# WiFi_Bluetooth_ESP-WROOM-32.net
KiCad netlist of a schematic drawn in Altium Designer
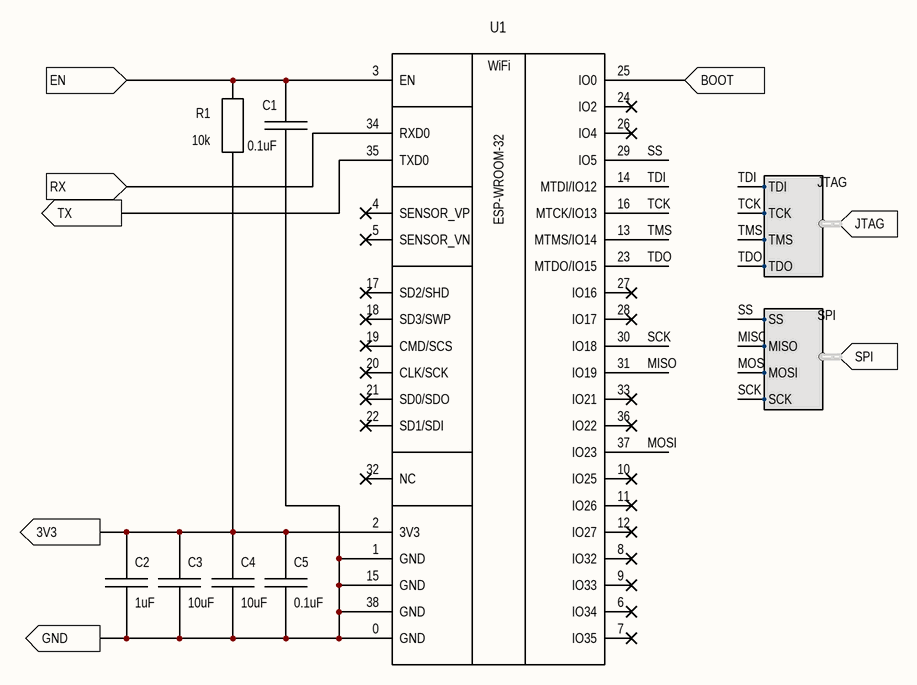
[diagram p0: WiFi Bluetooth ESP-WROOM-32.SchDoc]

(export (version "E")
  (design (tool "Eeschema 10.0.6"))
  (components
    (comp (ref "C1")
      (value "0.1uF")
      (footprint "CAPC1608L")
      (description "Capacitor Ceramic 0.1uF 25V 0603(1608)")
      (fields (field (name "TOLERANCE") "±10%") (field (name "VOLTAGE") "25"))
      (libsource (lib "Capacitors") (part "Capacitor Ceramic 0.1uF 25V 0603(1608)"))
    )
    (comp (ref "C2")
      (value "1uF")
      (footprint "CAPC1608L")
      (description "Capacitor Ceramic 1uF 25V 0603(1608)")
      (fields (field (name "TOLERANCE") "±10%") (field (name "VOLTAGE") "25V"))
      (libsource (lib "Capacitors") (part "Capacitor Ceramic 1uF 25V 0603(1608)"))
    )
    (comp (ref "C3")
      (value "10uF")
      (footprint "CAPC2012L")
      (description "Capacitor Ceramic 10uF 25V 0805(2012)")
      (fields (field (name "TOLERANCE") "±10%") (field (name "VOLTAGE") "25"))
      (libsource (lib "Capacitors") (part "Capacitor Ceramic 10uF 25V 0805(2012)"))
    )
    (comp (ref "C4")
      (value "10uF")
      (footprint "CAPC2012L")
      (description "Capacitor Ceramic 10uF 25V 0805(2012)")
      (fields (field (name "TOLERANCE") "±10%") (field (name "VOLTAGE") "25"))
      (libsource (lib "Capacitors") (part "Capacitor Ceramic 10uF 25V 0805(2012)"))
    )
    (comp (ref "C5")
      (value "0.1uF")
      (footprint "CAPC1608L")
      (description "Capacitor Ceramic 0.1uF 25V 0603(1608)")
      (fields (field (name "TOLERANCE") "±10%") (field (name "VOLTAGE") "25"))
      (libsource (lib "Capacitors") (part "Capacitor Ceramic 0.1uF 25V 0603(1608)"))
    )
    (comp (ref "R1")
      (value "10k")
      (footprint "RESC1608L")
      (description "Resistor Ceramic 10k 0.1W 0603(1608)")
      (fields (field (name "TOLERANCE") "±5%") (field (name "POWER") "0.1W"))
      (libsource (lib "Resistors") (part "Resistor Ceramic 10k 0.1W 0603(1608)"))
    )
    (comp (ref "U1")
      (value "ESP-WROOM-32")
      (description "WiFi/Bluetooth Module based on ESP32")
      (fields (field (name "MANUFACTURER") "Espressif"))
      (libsource (lib "Wireless") (part "ESP-WROOM-32"))
    )
  )
  (nets
    (net (code "3") (name "/3V3") (class "Default")
      (node (ref "C2") (pin "1") (pinfunction "1_1") (pintype "passive"))
      (node (ref "C3") (pin "1") (pinfunction "1_1") (pintype "passive"))
      (node (ref "C4") (pin "1") (pinfunction "1_1") (pintype "passive"))
      (node (ref "C5") (pin "1") (pinfunction "1_1") (pintype "passive"))
      (node (ref "R1") (pin "2") (pinfunction "2_2") (pintype "passive"))
      (node (ref "U1") (pin "2") (pinfunction "3V3_2") (pintype "passive"))
    )
    (net (code "4") (name "/BOOT") (class "Default")
      (node (ref "U1") (pin "25") (pinfunction "IO0_25") (pintype "passive"))
    )
    (net (code "5") (name "/EN") (class "Default")
      (node (ref "C1") (pin "1") (pinfunction "1_1") (pintype "passive"))
      (node (ref "R1") (pin "1") (pinfunction "1_1") (pintype "passive"))
      (node (ref "U1") (pin "3") (pinfunction "EN_3") (pintype "passive"))
    )
    (net (code "6") (name "/GND") (class "Default")
      (node (ref "C1") (pin "2") (pinfunction "2_2") (pintype "passive"))
      (node (ref "C2") (pin "2") (pinfunction "2_2") (pintype "passive"))
      (node (ref "C3") (pin "2") (pinfunction "2_2") (pintype "passive"))
      (node (ref "C4") (pin "2") (pinfunction "2_2") (pintype "passive"))
      (node (ref "C5") (pin "2") (pinfunction "2_2") (pintype "passive"))
      (node (ref "U1") (pin "0") (pinfunction "GND_0") (pintype "passive"))
      (node (ref "U1") (pin "1") (pinfunction "GND_1") (pintype "passive"))
      (node (ref "U1") (pin "15") (pinfunction "GND_15") (pintype "passive"))
      (node (ref "U1") (pin "38") (pinfunction "GND_38") (pintype "passive"))
    )
    (net (code "7") (name "/MISO") (class "Default")
      (node (ref "U1") (pin "31") (pinfunction "IO19_31") (pintype "passive"))
    )
    (net (code "8") (name "/MOSI") (class "Default")
      (node (ref "U1") (pin "37") (pinfunction "IO23_37") (pintype "passive"))
    )
    (net (code "9") (name "/RX") (class "Default")
      (node (ref "U1") (pin "34") (pinfunction "RXD0_34") (pintype "passive"))
    )
    (net (code "10") (name "/SCK") (class "Default")
      (node (ref "U1") (pin "30") (pinfunction "IO18_30") (pintype "passive"))
    )
    (net (code "11") (name "/SS") (class "Default")
      (node (ref "U1") (pin "29") (pinfunction "IO5_29") (pintype "passive"))
    )
    (net (code "12") (name "/TCK") (class "Default")
      (node (ref "U1") (pin "16") (pinfunction "MTCK/IO13_16") (pintype "passive"))
    )
    (net (code "13") (name "/TDI") (class "Default")
      (node (ref "U1") (pin "14") (pinfunction "MTDI/IO12_14") (pintype "passive"))
    )
    (net (code "14") (name "/TDO") (class "Default")
      (node (ref "U1") (pin "23") (pinfunction "MTDO/IO15_23") (pintype "passive"))
    )
    (net (code "15") (name "/TMS") (class "Default")
      (node (ref "U1") (pin "13") (pinfunction "MTMS/IO14_13") (pintype "passive"))
    )
    (net (code "16") (name "/TX") (class "Default")
      (node (ref "U1") (pin "35") (pinfunction "TXD0_35") (pintype "passive"))
    )
    (net (code "19") (name "unconnected-(U1-CLK{slash}SCK-Pad20)") (class "Default")
      (node (ref "U1") (pin "20") (pinfunction "CLK/SCK_20") (pintype "passive+no_connect"))
    )
    (net (code "20") (name "unconnected-(U1-CMD{slash}SCS-Pad19)") (class "Default")
      (node (ref "U1") (pin "19") (pinfunction "CMD/SCS_19") (pintype "passive+no_connect"))
    )
    (net (code "21") (name "unconnected-(U1-IO2-Pad24)") (class "Default")
      (node (ref "U1") (pin "24") (pinfunction "IO2_24") (pintype "passive+no_connect"))
    )
    (net (code "22") (name "unconnected-(U1-IO4-Pad26)") (class "Default")
      (node (ref "U1") (pin "26") (pinfunction "IO4_26") (pintype "passive+no_connect"))
    )
    (net (code "23") (name "unconnected-(U1-IO16-Pad27)") (class "Default")
      (node (ref "U1") (pin "27") (pinfunction "IO16_27") (pintype "passive+no_connect"))
    )
    (net (code "24") (name "unconnected-(U1-IO17-Pad28)") (class "Default")
      (node (ref "U1") (pin "28") (pinfunction "IO17_28") (pintype "passive+no_connect"))
    )
    (net (code "25") (name "unconnected-(U1-IO21-Pad33)") (class "Default")
      (node (ref "U1") (pin "33") (pinfunction "IO21_33") (pintype "passive+no_connect"))
    )
    (net (code "26") (name "unconnected-(U1-IO22-Pad36)") (class "Default")
      (node (ref "U1") (pin "36") (pinfunction "IO22_36") (pintype "passive+no_connect"))
    )
    (net (code "27") (name "unconnected-(U1-IO25-Pad10)") (class "Default")
      (node (ref "U1") (pin "10") (pinfunction "IO25_10") (pintype "passive+no_connect"))
    )
    (net (code "28") (name "unconnected-(U1-IO26-Pad11)") (class "Default")
      (node (ref "U1") (pin "11") (pinfunction "IO26_11") (pintype "passive+no_connect"))
    )
    (net (code "29") (name "unconnected-(U1-IO27-Pad12)") (class "Default")
      (node (ref "U1") (pin "12") (pinfunction "IO27_12") (pintype "passive+no_connect"))
    )
    (net (code "30") (name "unconnected-(U1-IO32-Pad8)") (class "Default")
      (node (ref "U1") (pin "8") (pinfunction "IO32_8") (pintype "passive+no_connect"))
    )
    (net (code "31") (name "unconnected-(U1-IO33-Pad9)") (class "Default")
      (node (ref "U1") (pin "9") (pinfunction "IO33_9") (pintype "passive+no_connect"))
    )
    (net (code "32") (name "unconnected-(U1-IO34-Pad6)") (class "Default")
      (node (ref "U1") (pin "6") (pinfunction "IO34_6") (pintype "passive+no_connect"))
    )
    (net (code "33") (name "unconnected-(U1-IO35-Pad7)") (class "Default")
      (node (ref "U1") (pin "7") (pinfunction "IO35_7") (pintype "passive+no_connect"))
    )
    (net (code "34") (name "unconnected-(U1-NC-Pad32)") (class "Default")
      (node (ref "U1") (pin "32") (pinfunction "NC_32") (pintype "passive+no_connect"))
    )
    (net (code "35") (name "unconnected-(U1-SD0{slash}SDO-Pad21)") (class "Default")
      (node (ref "U1") (pin "21") (pinfunction "SD0/SDO_21") (pintype "passive+no_connect"))
    )
    (net (code "36") (name "unconnected-(U1-SD1{slash}SDI-Pad22)") (class "Default")
      (node (ref "U1") (pin "22") (pinfunction "SD1/SDI_22") (pintype "passive+no_connect"))
    )
    (net (code "37") (name "unconnected-(U1-SD2{slash}SHD-Pad17)") (class "Default")
      (node (ref "U1") (pin "17") (pinfunction "SD2/SHD_17") (pintype "passive+no_connect"))
    )
    (net (code "38") (name "unconnected-(U1-SD3{slash}SWP-Pad18)") (class "Default")
      (node (ref "U1") (pin "18") (pinfunction "SD3/SWP_18") (pintype "passive+no_connect"))
    )
    (net (code "39") (name "unconnected-(U1-SENSOR_VN-Pad5)") (class "Default")
      (node (ref "U1") (pin "5") (pinfunction "SENSOR_VN_5") (pintype "passive+no_connect"))
    )
    (net (code "40") (name "unconnected-(U1-SENSOR_VP-Pad4)") (class "Default")
      (node (ref "U1") (pin "4") (pinfunction "SENSOR_VP_4") (pintype "passive+no_connect"))
    )
  )
)
